# layout4.net
KiCad netlist of a schematic drawn in EAGLE
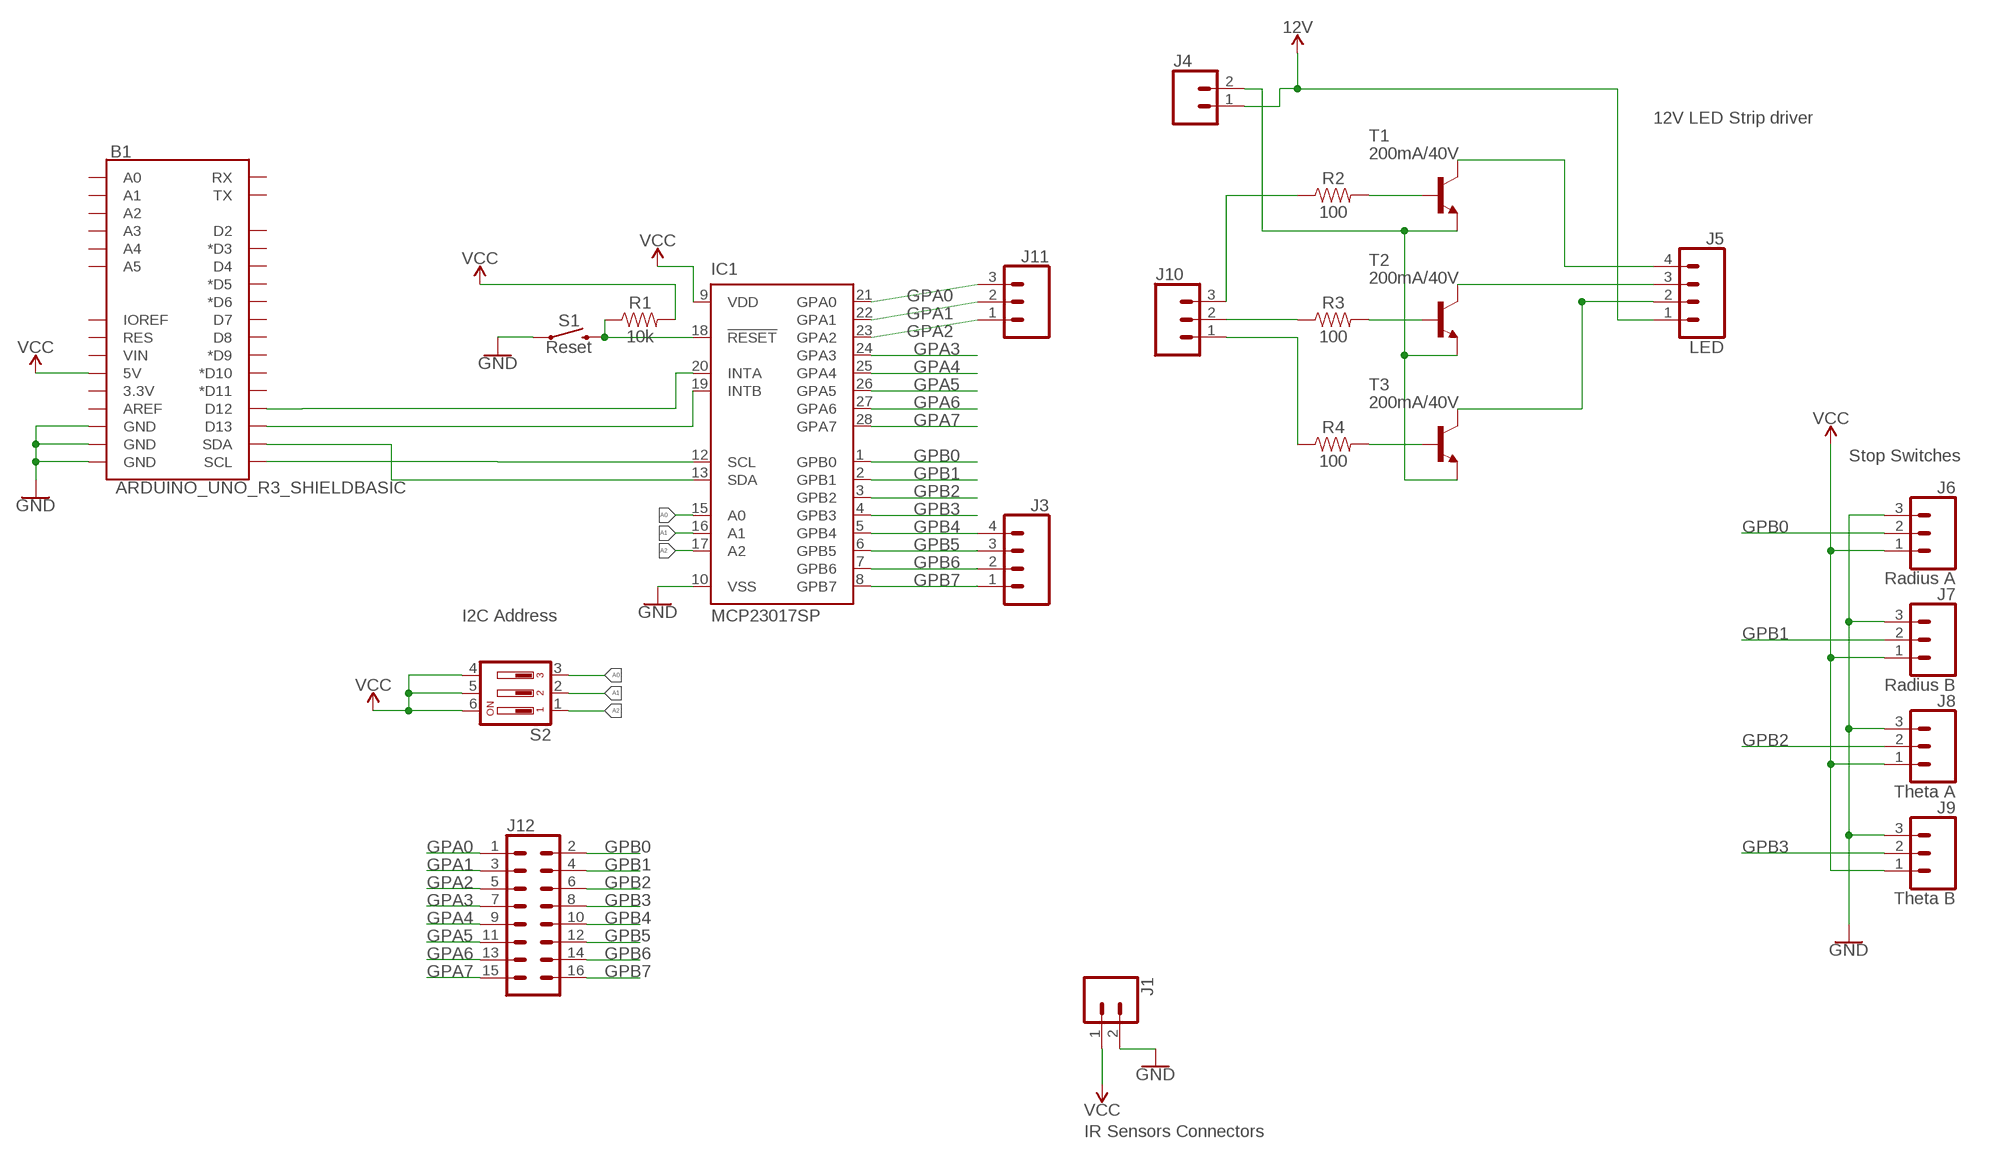
[diagram p0: schematic, sheet 1]

(export (version "E")
  (design (tool "Eeschema 10.0.6"))
  (components
    (comp (ref "B1")
      (value "ARDUINO_UNO_R3_SHIELDBASIC")
      (footprint "eagle-import:UNO_R3_SHIELD")
      (libsource (lib "eagle-import") (part "ARDUINO_UNO_R3_SHIELDBASIC"))
    )
    (comp (ref "IC1")
      (value "MCP23017SP")
      (footprint "eagle-import:DIL28-3")
      (libsource (lib "eagle-import") (part "MCP23017SP"))
    )
    (comp (ref "J1")
      (value "CONN_02POLAR")
      (footprint "eagle-import:MOLEX-1X2")
      (libsource (lib "eagle-import") (part "CONN_02POLAR"))
    )
    (comp (ref "J3")
      (value "CONN_04")
      (footprint "eagle-import:1X04")
      (libsource (lib "eagle-import") (part "CONN_04"))
    )
    (comp (ref "J4")
      (value "CONN_023.5MM")
      (footprint "eagle-import:SCREWTERMINAL-3.5MM-2")
      (libsource (lib "eagle-import") (part "CONN_023.5MM"))
    )
    (comp (ref "J5")
      (value "LED")
      (footprint "eagle-import:MOLEX-1X4")
      (libsource (lib "eagle-import") (part "CONN_04POLAR"))
    )
    (comp (ref "J6")
      (value "Radius A")
      (footprint "eagle-import:MOLEX-1X3")
      (libsource (lib "eagle-import") (part "CONN_03POLAR"))
    )
    (comp (ref "J7")
      (value "Radius B")
      (footprint "eagle-import:MOLEX-1X3")
      (libsource (lib "eagle-import") (part "CONN_03POLAR"))
    )
    (comp (ref "J8")
      (value "Theta A")
      (footprint "eagle-import:MOLEX-1X3")
      (libsource (lib "eagle-import") (part "CONN_03POLAR"))
    )
    (comp (ref "J9")
      (value "Theta B")
      (footprint "eagle-import:MOLEX-1X3")
      (libsource (lib "eagle-import") (part "CONN_03POLAR"))
    )
    (comp (ref "J10")
      (value "CONN_03")
      (footprint "eagle-import:1X03")
      (libsource (lib "eagle-import") (part "CONN_03"))
    )
    (comp (ref "J11")
      (value "CONN_03")
      (footprint "eagle-import:1X03")
      (libsource (lib "eagle-import") (part "CONN_03"))
    )
    (comp (ref "J12")
      (value "CONN_08X2")
      (footprint "eagle-import:2X8")
      (libsource (lib "eagle-import") (part "CONN_08X2"))
    )
    (comp (ref "R1")
      (value "10k")
      (footprint "eagle-import:0603")
      (libsource (lib "eagle-import") (part "10KOHM-0603-1/10W-1%"))
    )
    (comp (ref "R2")
      (value "100")
      (footprint "eagle-import:0603")
      (libsource (lib "eagle-import") (part "100OHM-0603-1/4W-5%"))
    )
    (comp (ref "R3")
      (value "100")
      (footprint "eagle-import:0603")
      (libsource (lib "eagle-import") (part "100OHM-0603-1/4W-5%"))
    )
    (comp (ref "R4")
      (value "100")
      (footprint "eagle-import:0603")
      (libsource (lib "eagle-import") (part "100OHM-0603-1/4W-5%"))
    )
    (comp (ref "S1")
      (value "Reset")
      (footprint "eagle-import:TACTILE_SWITCH_PTH_6.0MM")
      (libsource (lib "eagle-import") (part "MOMENTARY-SWITCH-SPST-PTH-6.0MM"))
    )
    (comp (ref "S2")
      (value "DS03")
      (footprint "eagle-import:DS-03")
      (libsource (lib "eagle-import") (part "DS03"))
    )
    (comp (ref "T1")
      (value "200mA/40V")
      (footprint "eagle-import:TO220")
      (libsource (lib "eagle-import") (part "-NPN-TO220"))
    )
    (comp (ref "T2")
      (value "200mA/40V")
      (footprint "eagle-import:TO220")
      (libsource (lib "eagle-import") (part "-NPN-TO220"))
    )
    (comp (ref "T3")
      (value "200mA/40V")
      (footprint "eagle-import:TO220")
      (libsource (lib "eagle-import") (part "-NPN-TO220"))
    )
  )
  (nets
    (net (code "1") (name "/GPA0") (class "Default")
      (node (ref "IC1") (pin "21") (pinfunction "GPA0_21") (pintype "bidirectional"))
      (node (ref "J11") (pin "3") (pinfunction "3_3") (pintype "passive"))
      (node (ref "J12") (pin "1") (pinfunction "1_1") (pintype "passive"))
    )
    (net (code "2") (name "/GPA1") (class "Default")
      (node (ref "IC1") (pin "22") (pinfunction "GPA1_22") (pintype "bidirectional"))
      (node (ref "J11") (pin "2") (pinfunction "2_2") (pintype "passive"))
      (node (ref "J12") (pin "3") (pinfunction "3_3") (pintype "passive"))
    )
    (net (code "3") (name "/GPA2") (class "Default")
      (node (ref "IC1") (pin "23") (pinfunction "GPA2_23") (pintype "bidirectional"))
      (node (ref "J11") (pin "1") (pinfunction "1_1") (pintype "passive"))
      (node (ref "J12") (pin "5") (pinfunction "5_5") (pintype "passive"))
    )
    (net (code "4") (name "/GPA3") (class "Default")
      (node (ref "IC1") (pin "24") (pinfunction "GPA3_24") (pintype "bidirectional"))
      (node (ref "J12") (pin "7") (pinfunction "7_7") (pintype "passive"))
    )
    (net (code "5") (name "/GPA4") (class "Default")
      (node (ref "IC1") (pin "25") (pinfunction "GPA4_25") (pintype "bidirectional"))
      (node (ref "J12") (pin "9") (pinfunction "9_9") (pintype "passive"))
    )
    (net (code "6") (name "/GPA5") (class "Default")
      (node (ref "IC1") (pin "26") (pinfunction "GPA5_26") (pintype "bidirectional"))
      (node (ref "J12") (pin "11") (pinfunction "11_11") (pintype "passive"))
    )
    (net (code "7") (name "/GPA6") (class "Default")
      (node (ref "IC1") (pin "27") (pinfunction "GPA6_27") (pintype "bidirectional"))
      (node (ref "J12") (pin "13") (pinfunction "13_13") (pintype "passive"))
    )
    (net (code "8") (name "/GPA7") (class "Default")
      (node (ref "IC1") (pin "28") (pinfunction "GPA7_28") (pintype "bidirectional"))
      (node (ref "J12") (pin "15") (pinfunction "15_15") (pintype "passive"))
    )
    (net (code "9") (name "/GPB0") (class "Default")
      (node (ref "IC1") (pin "1") (pinfunction "GPB0_1") (pintype "bidirectional"))
      (node (ref "J12") (pin "2") (pinfunction "2_2") (pintype "passive"))
      (node (ref "J6") (pin "2") (pinfunction "2_2") (pintype "passive"))
    )
    (net (code "10") (name "/GPB1") (class "Default")
      (node (ref "IC1") (pin "2") (pinfunction "GPB1_2") (pintype "bidirectional"))
      (node (ref "J12") (pin "4") (pinfunction "4_4") (pintype "passive"))
      (node (ref "J7") (pin "2") (pinfunction "2_2") (pintype "passive"))
    )
    (net (code "11") (name "/GPB2") (class "Default")
      (node (ref "IC1") (pin "3") (pinfunction "GPB2_3") (pintype "bidirectional"))
      (node (ref "J12") (pin "6") (pinfunction "6_6") (pintype "passive"))
      (node (ref "J8") (pin "2") (pinfunction "2_2") (pintype "passive"))
    )
    (net (code "12") (name "/GPB3") (class "Default")
      (node (ref "IC1") (pin "4") (pinfunction "GPB3_4") (pintype "bidirectional"))
      (node (ref "J12") (pin "8") (pinfunction "8_8") (pintype "passive"))
      (node (ref "J9") (pin "2") (pinfunction "2_2") (pintype "passive"))
    )
    (net (code "13") (name "/GPB4") (class "Default")
      (node (ref "IC1") (pin "5") (pinfunction "GPB4_5") (pintype "bidirectional"))
      (node (ref "J12") (pin "10") (pinfunction "10_10") (pintype "passive"))
      (node (ref "J3") (pin "4") (pinfunction "4_4") (pintype "passive"))
    )
    (net (code "14") (name "/GPB5") (class "Default")
      (node (ref "IC1") (pin "6") (pinfunction "GPB5_6") (pintype "bidirectional"))
      (node (ref "J12") (pin "12") (pinfunction "12_12") (pintype "passive"))
      (node (ref "J3") (pin "3") (pinfunction "3_3") (pintype "passive"))
    )
    (net (code "15") (name "/GPB6") (class "Default")
      (node (ref "IC1") (pin "7") (pinfunction "GPB6_7") (pintype "bidirectional"))
      (node (ref "J12") (pin "14") (pinfunction "14_14") (pintype "passive"))
      (node (ref "J3") (pin "2") (pinfunction "2_2") (pintype "passive"))
    )
    (net (code "16") (name "/GPB7") (class "Default")
      (node (ref "IC1") (pin "8") (pinfunction "GPB7_8") (pintype "bidirectional"))
      (node (ref "J12") (pin "16") (pinfunction "16_16") (pintype "passive"))
      (node (ref "J3") (pin "1") (pinfunction "1_1") (pintype "passive"))
    )
    (net (code "17") (name "12V") (class "Default")
      (node (ref "J4") (pin "1") (pinfunction "1_1") (pintype "passive"))
      (node (ref "J5") (pin "1") (pinfunction "1_1") (pintype "passive"))
    )
    (net (code "18") (name "A0") (class "Default")
      (node (ref "IC1") (pin "15") (pinfunction "A0_15") (pintype "input"))
      (node (ref "S2") (pin "3") (pinfunction "3_3") (pintype "passive"))
    )
    (net (code "19") (name "A1") (class "Default")
      (node (ref "IC1") (pin "16") (pinfunction "A1_16") (pintype "input"))
      (node (ref "S2") (pin "2") (pinfunction "2_2") (pintype "passive"))
    )
    (net (code "20") (name "A2") (class "Default")
      (node (ref "IC1") (pin "17") (pinfunction "A2_17") (pintype "input"))
      (node (ref "S2") (pin "1") (pinfunction "1_1") (pintype "passive"))
    )
    (net (code "21") (name "GND") (class "Default")
      (node (ref "B1") (pin "GND@0") (pinfunction "GND_GND@0") (pintype "bidirectional"))
      (node (ref "B1") (pin "GND@1") (pinfunction "GND_GND@1") (pintype "bidirectional"))
      (node (ref "B1") (pin "GND@2") (pinfunction "GND_GND@2") (pintype "bidirectional"))
      (node (ref "IC1") (pin "10") (pinfunction "VSS_10") (pintype "power_in"))
      (node (ref "J1") (pin "2") (pinfunction "2_2") (pintype "passive"))
      (node (ref "J6") (pin "3") (pinfunction "3_3") (pintype "passive"))
      (node (ref "J7") (pin "3") (pinfunction "3_3") (pintype "passive"))
      (node (ref "J8") (pin "3") (pinfunction "3_3") (pintype "passive"))
      (node (ref "J9") (pin "3") (pinfunction "3_3") (pintype "passive"))
      (node (ref "S1") (pin "1") (pinfunction "1_1") (pintype "passive"))
    )
    (net (code "22") (name "Net-(IC1-INTA)") (class "Default")
      (node (ref "B1") (pin "D12") (pinfunction "D12_D12") (pintype "bidirectional"))
      (node (ref "IC1") (pin "20") (pinfunction "INTA_20") (pintype "output"))
    )
    (net (code "23") (name "Net-(IC1-INTB)") (class "Default")
      (node (ref "B1") (pin "D13") (pinfunction "D13_D13") (pintype "bidirectional"))
      (node (ref "IC1") (pin "19") (pinfunction "INTB_19") (pintype "output"))
    )
    (net (code "24") (name "Net-(IC1-SCL)") (class "Default")
      (node (ref "B1") (pin "SCL") (pinfunction "SCL_SCL") (pintype "bidirectional"))
      (node (ref "IC1") (pin "12") (pinfunction "SCL_12") (pintype "input"))
    )
    (net (code "25") (name "Net-(IC1-SDA)") (class "Default")
      (node (ref "B1") (pin "SDA") (pinfunction "SDA_SDA") (pintype "bidirectional"))
      (node (ref "IC1") (pin "13") (pinfunction "SDA_13") (pintype "bidirectional"))
    )
    (net (code "26") (name "Net-(IC1-~{RESET})") (class "Default")
      (node (ref "IC1") (pin "18") (pinfunction "~{RESET}_18") (pintype "input"))
      (node (ref "R1") (pin "1") (pinfunction "1_1") (pintype "passive"))
      (node (ref "S1") (pin "3") (pinfunction "2_3") (pintype "passive"))
    )
    (net (code "27") (name "Net-(J10-Pad1)") (class "Default")
      (node (ref "J10") (pin "1") (pinfunction "1_1") (pintype "passive"))
      (node (ref "R4") (pin "1") (pinfunction "1_1") (pintype "passive"))
    )
    (net (code "28") (name "Net-(J10-Pad2)") (class "Default")
      (node (ref "J10") (pin "2") (pinfunction "2_2") (pintype "passive"))
      (node (ref "R3") (pin "1") (pinfunction "1_1") (pintype "passive"))
    )
    (net (code "29") (name "Net-(J10-Pad3)") (class "Default")
      (node (ref "J10") (pin "3") (pinfunction "3_3") (pintype "passive"))
      (node (ref "R2") (pin "1") (pinfunction "1_1") (pintype "passive"))
    )
    (net (code "30") (name "Net-(T1-B)") (class "Default")
      (node (ref "R2") (pin "2") (pinfunction "2_2") (pintype "passive"))
      (node (ref "T1") (pin "1") (pinfunction "B_1") (pintype "passive"))
    )
    (net (code "31") (name "Net-(T1-C)") (class "Default")
      (node (ref "J5") (pin "4") (pinfunction "4_4") (pintype "passive"))
      (node (ref "T1") (pin "2") (pinfunction "C_2") (pintype "passive"))
    )
    (net (code "32") (name "Net-(T1-E)") (class "Default")
      (node (ref "J4") (pin "2") (pinfunction "2_2") (pintype "passive"))
      (node (ref "T1") (pin "3") (pinfunction "E_3") (pintype "passive"))
      (node (ref "T2") (pin "3") (pinfunction "E_3") (pintype "passive"))
      (node (ref "T3") (pin "3") (pinfunction "E_3") (pintype "passive"))
    )
    (net (code "33") (name "Net-(T2-B)") (class "Default")
      (node (ref "R3") (pin "2") (pinfunction "2_2") (pintype "passive"))
      (node (ref "T2") (pin "1") (pinfunction "B_1") (pintype "passive"))
    )
    (net (code "34") (name "Net-(T2-C)") (class "Default")
      (node (ref "J5") (pin "3") (pinfunction "3_3") (pintype "passive"))
      (node (ref "T2") (pin "2") (pinfunction "C_2") (pintype "passive"))
    )
    (net (code "35") (name "Net-(T3-B)") (class "Default")
      (node (ref "R4") (pin "2") (pinfunction "2_2") (pintype "passive"))
      (node (ref "T3") (pin "1") (pinfunction "B_1") (pintype "passive"))
    )
    (net (code "36") (name "Net-(T3-C)") (class "Default")
      (node (ref "J5") (pin "2") (pinfunction "2_2") (pintype "passive"))
      (node (ref "T3") (pin "2") (pinfunction "C_2") (pintype "passive"))
    )
    (net (code "37") (name "VCC") (class "Default")
      (node (ref "B1") (pin "5V") (pinfunction "5V_5V") (pintype "bidirectional"))
      (node (ref "IC1") (pin "9") (pinfunction "VDD_9") (pintype "power_in"))
      (node (ref "J1") (pin "1") (pinfunction "1_1") (pintype "passive"))
      (node (ref "J6") (pin "1") (pinfunction "1_1") (pintype "passive"))
      (node (ref "J7") (pin "1") (pinfunction "1_1") (pintype "passive"))
      (node (ref "J8") (pin "1") (pinfunction "1_1") (pintype "passive"))
      (node (ref "J9") (pin "1") (pinfunction "1_1") (pintype "passive"))
      (node (ref "R1") (pin "2") (pinfunction "2_2") (pintype "passive"))
      (node (ref "S2") (pin "4") (pinfunction "4_4") (pintype "passive"))
      (node (ref "S2") (pin "5") (pinfunction "5_5") (pintype "passive"))
      (node (ref "S2") (pin "6") (pinfunction "6_6") (pintype "passive"))
    )
    (net (code "38") (name "unconnected-(B1-*D3-PadD3)") (class "Default")
      (node (ref "B1") (pin "D3") (pinfunction "*D3_D3") (pintype "bidirectional"))
    )
    (net (code "39") (name "unconnected-(B1-*D5-PadD5)") (class "Default")
      (node (ref "B1") (pin "D5") (pinfunction "*D5_D5") (pintype "bidirectional"))
    )
    (net (code "40") (name "unconnected-(B1-*D6-PadD6)") (class "Default")
      (node (ref "B1") (pin "D6") (pinfunction "*D6_D6") (pintype "bidirectional"))
    )
    (net (code "41") (name "unconnected-(B1-*D9-PadD9)") (class "Default")
      (node (ref "B1") (pin "D9") (pinfunction "*D9_D9") (pintype "bidirectional"))
    )
    (net (code "42") (name "unconnected-(B1-*D10-PadD10)") (class "Default")
      (node (ref "B1") (pin "D10") (pinfunction "*D10_D10") (pintype "bidirectional"))
    )
    (net (code "43") (name "unconnected-(B1-*D11-PadD11)") (class "Default")
      (node (ref "B1") (pin "D11") (pinfunction "*D11_D11") (pintype "bidirectional"))
    )
    (net (code "44") (name "unconnected-(B1-Pad3.3V)") (class "Default")
      (node (ref "B1") (pin "3.3V") (pinfunction "3.3V_3.3V") (pintype "bidirectional"))
    )
    (net (code "45") (name "unconnected-(B1-PadA0)") (class "Default")
      (node (ref "B1") (pin "A0") (pinfunction "A0_A0") (pintype "bidirectional"))
    )
    (net (code "46") (name "unconnected-(B1-PadA1)") (class "Default")
      (node (ref "B1") (pin "A1") (pinfunction "A1_A1") (pintype "bidirectional"))
    )
    (net (code "47") (name "unconnected-(B1-PadA2)") (class "Default")
      (node (ref "B1") (pin "A2") (pinfunction "A2_A2") (pintype "bidirectional"))
    )
    (net (code "48") (name "unconnected-(B1-PadA3)") (class "Default")
      (node (ref "B1") (pin "A3") (pinfunction "A3_A3") (pintype "bidirectional"))
    )
    (net (code "49") (name "unconnected-(B1-PadA4)") (class "Default")
      (node (ref "B1") (pin "A4") (pinfunction "A4_A4") (pintype "bidirectional"))
    )
    (net (code "50") (name "unconnected-(B1-PadA5)") (class "Default")
      (node (ref "B1") (pin "A5") (pinfunction "A5_A5") (pintype "bidirectional"))
    )
    (net (code "51") (name "unconnected-(B1-PadAREF)") (class "Default")
      (node (ref "B1") (pin "AREF") (pinfunction "AREF_AREF") (pintype "bidirectional"))
    )
    (net (code "52") (name "unconnected-(B1-PadD2)") (class "Default")
      (node (ref "B1") (pin "D2") (pinfunction "D2_D2") (pintype "bidirectional"))
    )
    (net (code "53") (name "unconnected-(B1-PadD4)") (class "Default")
      (node (ref "B1") (pin "D4") (pinfunction "D4_D4") (pintype "bidirectional"))
    )
    (net (code "54") (name "unconnected-(B1-PadD7)") (class "Default")
      (node (ref "B1") (pin "D7") (pinfunction "D7_D7") (pintype "bidirectional"))
    )
    (net (code "55") (name "unconnected-(B1-PadD8)") (class "Default")
      (node (ref "B1") (pin "D8") (pinfunction "D8_D8") (pintype "bidirectional"))
    )
    (net (code "56") (name "unconnected-(B1-PadIOREF)") (class "Default")
      (node (ref "B1") (pin "IOREF") (pinfunction "IOREF_IOREF") (pintype "bidirectional"))
    )
    (net (code "57") (name "unconnected-(B1-PadRES)") (class "Default")
      (node (ref "B1") (pin "RES") (pinfunction "RES_RES") (pintype "bidirectional"))
    )
    (net (code "58") (name "unconnected-(B1-PadRX)") (class "Default")
      (node (ref "B1") (pin "RX") (pinfunction "RX_RX") (pintype "bidirectional"))
    )
    (net (code "59") (name "unconnected-(B1-PadTX)") (class "Default")
      (node (ref "B1") (pin "TX") (pinfunction "TX_TX") (pintype "bidirectional"))
    )
    (net (code "60") (name "unconnected-(B1-PadVIN)") (class "Default")
      (node (ref "B1") (pin "VIN") (pinfunction "VIN_VIN") (pintype "bidirectional"))
    )
  )
)
